# DCDC_LIN_CONN.net
KiCad netlist of a schematic drawn in Altium Designer
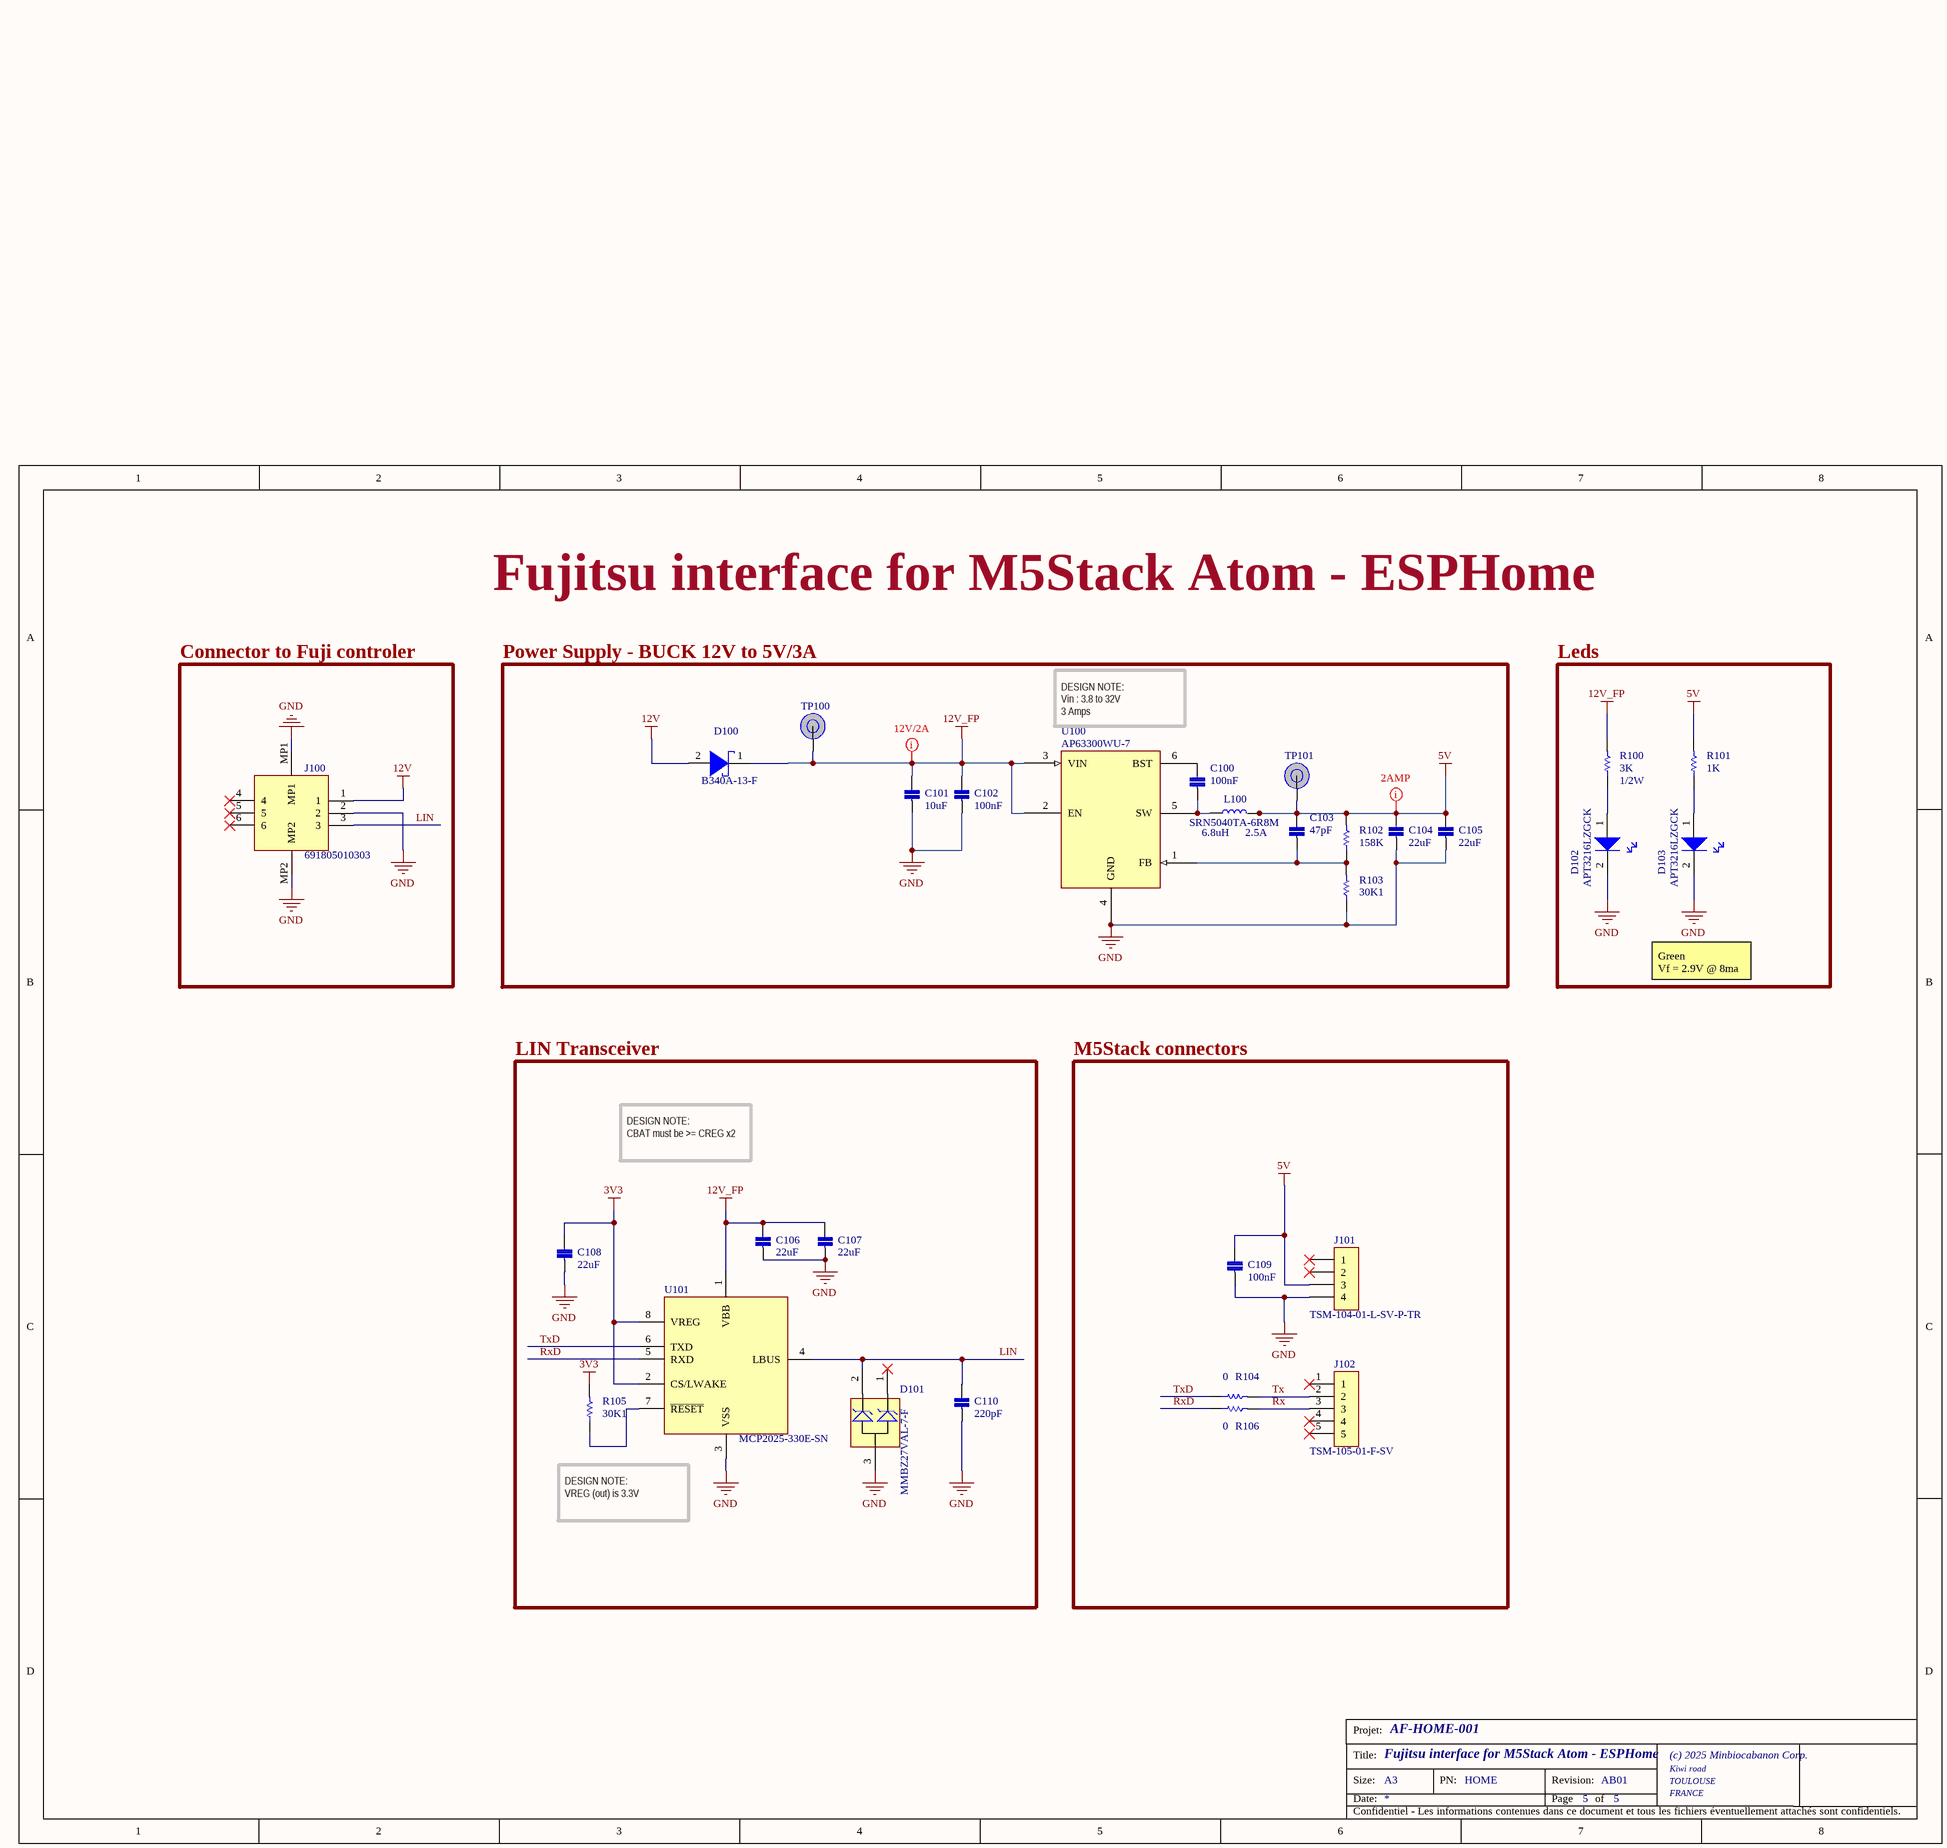
[diagram p0: DCDC_LIN_CONN.SchDoc]

(export (version "E")
  (design (tool "Eeschema 10.0.6"))
  (components
    (comp (ref "C100")
      (value "100nF")
      (footprint "0603_CAPA")
      (description "100nF_50V_0603_5%_X7R")
      (fields
        (field (name "MANUFACTURER PART NUMBER") "CAPA_CMS_100nF_50V_0603_5%_X7R")
        (field (name "TOLERANCE") "5%")
      )
      (libsource (lib "OILibrary") (part "CAPA_CMS-Generique"))
    )
    (comp (ref "C101")
      (value "10uF")
      (footprint "1206_CAPA")
      (description "10uF_50V_1206_10%_X7R")
      (fields
        (field (name "MANUFACTURER PART NUMBER") "CAPA_CMS_10uF_50V_1206_10%_X7R")
        (field (name "TOLERANCE") "10%")
      )
      (libsource (lib "OILibrary") (part "CAPA_CMS-Generique"))
    )
    (comp (ref "C102")
      (value "100nF")
      (footprint "0603_CAPA")
      (description "100nF_50V_0603_5%_X7R")
      (fields
        (field (name "MANUFACTURER PART NUMBER") "CAPA_CMS_100nF_50V_0603_5%_X7R")
        (field (name "TOLERANCE") "5%")
      )
      (libsource (lib "OILibrary") (part "CAPA_CMS-Generique"))
    )
    (comp (ref "C103")
      (value "47pF")
      (footprint "0603_CAPA")
      (description "47pF_50V_0603_5%_X7R")
      (fields
        (field (name "MANUFACTURER PART NUMBER") "CAPA_CMS_47pF_50V_0603_5%_X7R")
        (field (name "TOLERANCE") "5%")
      )
      (libsource (lib "OILibrary") (part "CAPA_CMS-Generique"))
    )
    (comp (ref "C104")
      (value "22uF")
      (footprint "0805_CAPA")
      (description "22uF_16V_0805_10%_X5R")
      (fields
        (field (name "MANUFACTURER PART NUMBER") "CAPA_CMS_22uF_16V_0805_10%_X5R")
        (field (name "TOLERANCE") "10%")
      )
      (libsource (lib "OILibrary") (part "CAPA_CMS-Generique"))
    )
    (comp (ref "C105")
      (value "22uF")
      (footprint "0805_CAPA")
      (description "22uF_16V_0805_10%_X5R")
      (fields
        (field (name "MANUFACTURER PART NUMBER") "CAPA_CMS_22uF_16V_0805_10%_X5R")
        (field (name "TOLERANCE") "10%")
      )
      (libsource (lib "OILibrary") (part "CAPA_CMS-Generique"))
    )
    (comp (ref "C106")
      (value "22uF")
      (footprint "0805_CAPA")
      (description "22uF_16V_0805_10%_X5R")
      (fields
        (field (name "MANUFACTURER PART NUMBER") "CAPA_CMS_22uF_16V_0805_10%_X5R")
        (field (name "TOLERANCE") "10%")
      )
      (libsource (lib "OILibrary") (part "CAPA_CMS-Generique"))
    )
    (comp (ref "C107")
      (value "22uF")
      (footprint "0805_CAPA")
      (description "22uF_16V_0805_10%_X5R")
      (fields
        (field (name "MANUFACTURER PART NUMBER") "CAPA_CMS_22uF_16V_0805_10%_X5R")
        (field (name "TOLERANCE") "10%")
      )
      (libsource (lib "OILibrary") (part "CAPA_CMS-Generique"))
    )
    (comp (ref "C108")
      (value "22uF")
      (footprint "0805_CAPA")
      (description "22uF_16V_0805_10%_X5R")
      (fields
        (field (name "MANUFACTURER PART NUMBER") "CAPA_CMS_22uF_16V_0805_10%_X5R")
        (field (name "TOLERANCE") "10%")
      )
      (libsource (lib "OILibrary") (part "CAPA_CMS-Generique"))
    )
    (comp (ref "C109")
      (value "100nF")
      (footprint "0603_CAPA")
      (description "100nF_50V_0603_5%_X7R")
      (fields
        (field (name "MANUFACTURER PART NUMBER") "CAPA_CMS_100nF_50V_0603_5%_X7R")
        (field (name "TOLERANCE") "5%")
      )
      (libsource (lib "OILibrary") (part "CAPA_CMS-Generique"))
    )
    (comp (ref "C110")
      (value "220pF")
      (footprint "0603_CAPA")
      (description "220pF_50V_0603_10%_X7R")
      (fields
        (field (name "MANUFACTURER PART NUMBER") "CAPA_CMS_220pF_50V_0603_10%_X7R")
        (field (name "TOLERANCE") "10%")
      )
      (libsource (lib "OILibrary") (part "CAPA_CMS-Generique"))
    )
    (comp (ref "D100")
      (value "B340A-13-F")
      (footprint "DIODE_B340A-13-F")
      (description "Diodes et redresseurs Schottky 40V 3A")
      (fields (field (name "MANUFACTURER") "Diodes"))
      (libsource (lib "OILibrary") (part "DIODE_SCHOTTKY_CMS-Generique"))
    )
    (comp (ref "D101")
      (value "MMBZ27VAL-7-F")
      (footprint "ESD_MMBZ27VAL-7-F")
      (description "Suppresseurs ESD / diodes TVS 27V 225mW")
      (libsource (lib "OILibrary") (part "ESD_MMBZ27VAL-7-F"))
    )
    (comp (ref "D102")
      (value "APT3216LZGCK")
      (footprint "LED_APT3216LZGCK")
      (description "LED CMS Green 3.2x1.6mm")
      (fields (field (name "MANUFACTURER") "Kingbright"))
      (libsource (lib "OILibrary") (part "LED_CMS-Generique"))
    )
    (comp (ref "D103")
      (value "APT3216LZGCK")
      (footprint "LED_APT3216LZGCK")
      (description "LED CMS Green 3.2x1.6mm")
      (fields (field (name "MANUFACTURER") "Kingbright"))
      (libsource (lib "OILibrary") (part "LED_CMS-Generique"))
    )
    (comp (ref "J100")
      (value "691805010303")
      (footprint "691805010303")
      (description "WR-TBL Series 8050 - 3 pins 2.50 mm Screwless SMT")
      (fields (field (name "MANUFACTURER") "Wurth Elektronik"))
      (libsource (lib "OILibrary") (part "691805010303"))
    )
    (comp (ref "J101")
      (value "TSM-104-01-L-SV-P-TR")
      (footprint "TSM-104-01-L-SV-P-TR")
      (description "Header male SMD 1x4")
      (fields (field (name "MANUFACTURER") "Samtec"))
      (libsource (lib "OILibrary") (part "TSM-104-01-L-SV-P-TR"))
    )
    (comp (ref "J102")
      (value "TSM-105-01-F-SV")
      (footprint "TSM-105-01-F-SV")
      (description "Header male SMD 1x5")
      (fields (field (name "MANUFACTURER") "SAMTEC"))
      (libsource (lib "OILibrary") (part "TSM-105-01-F-SV"))
    )
    (comp (ref "L100")
      (value "SRN5040TA-6R8M")
      (footprint "INDUCTOR_652-SRN5040TA-100M")
      (description "Inductance fixes 6.8uH 2.5A")
      (fields
        (field (name "MANUFACTURER") "Bourns")
        (field (name "INDUCTANCE") "6.8uH")
        (field (name "CURRENT RATING") "2.5A")
      )
      (libsource (lib "OILibrary") (part "INDUCTOR_CMS-Generique"))
    )
    (comp (ref "R100")
      (value "3K")
      (footprint "0805_RES")
      (description "3K_1/8W_0805_1%")
      (fields
        (field (name "MANUFACTURER PART NUMBER") "RES_CMS_3K_1/8W_0805_1%")
        (field (name "TOLERANCE") "1%")
      )
      (libsource (lib "OILibrary") (part "RES_CMS-Generique"))
    )
    (comp (ref "R101")
      (value "1K")
      (footprint "0603_RES")
      (description "1K_1/10W_0603_1%")
      (fields
        (field (name "MANUFACTURER PART NUMBER") "RES_CMS_1K_1/10W_0603_1%")
        (field (name "TOLERANCE") "1%")
      )
      (libsource (lib "OILibrary") (part "RES_CMS-Generique"))
    )
    (comp (ref "R102")
      (value "158K")
      (footprint "0603_RES")
      (description "158K_1/16W_0603_1%")
      (fields
        (field (name "MANUFACTURER PART NUMBER") "RES_CMS_158K_1/16W_0603_1%")
        (field (name "TOLERANCE") "1%")
      )
      (libsource (lib "OILibrary") (part "RES_CMS-Generique"))
    )
    (comp (ref "R103")
      (value "30K1")
      (footprint "0603_RES")
      (description "30K1_1/10W_0603_1%")
      (fields
        (field (name "MANUFACTURER PART NUMBER") "RES_CMS_30K1_1/10W_0603_1%")
        (field (name "TOLERANCE") "1%")
      )
      (libsource (lib "OILibrary") (part "RES_CMS-Generique"))
    )
    (comp (ref "R104")
      (value "0")
      (footprint "0603_RES")
      (description "0_1/10W_0603_1%")
      (fields
        (field (name "MANUFACTURER PART NUMBER") "RES_CMS_0_1/10W_0603_1%")
        (field (name "TOLERANCE") "1%")
      )
      (libsource (lib "OILibrary") (part "RES_CMS-Generique"))
    )
    (comp (ref "R105")
      (value "30K1")
      (footprint "0603_RES")
      (description "30K1_1/10W_0603_1%")
      (fields
        (field (name "MANUFACTURER PART NUMBER") "RES_CMS_30K1_1/10W_0603_1%")
        (field (name "TOLERANCE") "1%")
      )
      (libsource (lib "OILibrary") (part "RES_CMS-Generique"))
    )
    (comp (ref "R106")
      (value "0")
      (footprint "0603_RES")
      (description "0_1/10W_0603_1%")
      (fields
        (field (name "MANUFACTURER PART NUMBER") "RES_CMS_0_1/10W_0603_1%")
        (field (name "TOLERANCE") "1%")
      )
      (libsource (lib "OILibrary") (part "RES_CMS-Generique"))
    )
    (comp (ref "TP100")
      (value "5V_BUCK")
      (footprint "PTEST")
      (description "Test point")
      (fields (field (name "MANUFACTURER") "OPENINDUS") (field (name "MANUFACTURER PART NUMBER") "PTEST"))
      (libsource (lib "OILibrary") (part "PTEST"))
    )
    (comp (ref "TP101")
      (value "5V_BUCK")
      (footprint "PTEST")
      (description "Test point")
      (fields (field (name "MANUFACTURER") "OPENINDUS") (field (name "MANUFACTURER PART NUMBER") "PTEST"))
      (libsource (lib "OILibrary") (part "PTEST"))
    )
    (comp (ref "U100")
      (value "AP63300WU-7")
      (footprint "POWER_BUCK_AP63300WU-7")
      (description "Régulateurs de tension de commutation DCDC Conv HV Buck TSOT26 T&R 3K")
      (fields (field (name "MANUFACTURER") "Diodes Incorporated"))
      (libsource (lib "OILibrary") (part "POWER_BUCK_AP63300WU-7"))
    )
    (comp (ref "U101")
      (value "MCP2025-330E-SN")
      (footprint "MCP2025-330E-SN")
      (description "LIN Transceiver with Voltage Regulator SOIC 3.3V")
      (fields
        (field (name "MANUFACTURER PART NUMBER") "MCP2025-330E/SN")
        (field (name "MANUFACTURER") "Microchip")
      )
      (libsource (lib "OILibrary") (part "MCP2025-330E-SN"))
    )
  )
  (nets
    (net (code "1") (name "/LIN") (class "Default")
      (node (ref "C110") (pin "1") (pinfunction "1_1") (pintype "passive"))
      (node (ref "D101") (pin "2") (pinfunction "2_2") (pintype "passive"))
      (node (ref "J100") (pin "3") (pinfunction "3_3") (pintype "passive"))
      (node (ref "U101") (pin "4") (pinfunction "LBUS_4") (pintype "passive"))
    )
    (net (code "2") (name "/Rx") (class "Default")
      (node (ref "J102") (pin "3") (pinfunction "3_3") (pintype "passive"))
      (node (ref "R106") (pin "2") (pinfunction "2_2") (pintype "passive"))
    )
    (net (code "3") (name "/RxD") (class "Default")
      (node (ref "R106") (pin "1") (pinfunction "1_1") (pintype "passive"))
      (node (ref "U101") (pin "5") (pinfunction "RXD_5") (pintype "passive"))
    )
    (net (code "4") (name "/Tx") (class "Default")
      (node (ref "J102") (pin "2") (pinfunction "2_2") (pintype "passive"))
      (node (ref "R104") (pin "2") (pinfunction "2_2") (pintype "passive"))
    )
    (net (code "5") (name "/TxD") (class "Default")
      (node (ref "R104") (pin "1") (pinfunction "1_1") (pintype "passive"))
      (node (ref "U101") (pin "6") (pinfunction "TXD_6") (pintype "passive"))
    )
    (net (code "6") (name "3V3") (class "Default")
      (node (ref "C108") (pin "1") (pinfunction "1_1") (pintype "passive"))
      (node (ref "R105") (pin "2") (pinfunction "2_2") (pintype "passive"))
      (node (ref "U101") (pin "2") (pinfunction "CS/LWAKE_2") (pintype "passive"))
      (node (ref "U101") (pin "8") (pinfunction "VREG_8") (pintype "passive"))
    )
    (net (code "7") (name "5V") (class "Default")
      (node (ref "C103") (pin "1") (pinfunction "1_1") (pintype "passive"))
      (node (ref "C104") (pin "1") (pinfunction "1_1") (pintype "passive"))
      (node (ref "C105") (pin "1") (pinfunction "1_1") (pintype "passive"))
      (node (ref "C109") (pin "1") (pinfunction "1_1") (pintype "passive"))
      (node (ref "J101") (pin "3") (pinfunction "3_3") (pintype "passive"))
      (node (ref "L100") (pin "2") (pinfunction "2_2") (pintype "passive"))
      (node (ref "R101") (pin "2") (pinfunction "2_2") (pintype "passive"))
      (node (ref "R102") (pin "2") (pinfunction "2_2") (pintype "passive"))
      (node (ref "TP101") (pin "1") (pinfunction "1_1") (pintype "passive"))
    )
    (net (code "8") (name "12V") (class "Default")
      (node (ref "D100") (pin "2") (pinfunction "A_2") (pintype "passive"))
      (node (ref "J100") (pin "1") (pinfunction "1_1") (pintype "passive"))
    )
    (net (code "9") (name "12V_FP") (class "Default")
      (node (ref "C101") (pin "1") (pinfunction "1_1") (pintype "passive"))
      (node (ref "C102") (pin "1") (pinfunction "1_1") (pintype "passive"))
      (node (ref "C106") (pin "1") (pinfunction "1_1") (pintype "passive"))
      (node (ref "C107") (pin "1") (pinfunction "1_1") (pintype "passive"))
      (node (ref "D100") (pin "1") (pinfunction "K_1") (pintype "passive"))
      (node (ref "R100") (pin "2") (pinfunction "2_2") (pintype "passive"))
      (node (ref "TP100") (pin "1") (pinfunction "1_1") (pintype "passive"))
      (node (ref "U100") (pin "2") (pinfunction "EN_2") (pintype "passive"))
      (node (ref "U100") (pin "3") (pinfunction "VIN_3") (pintype "input"))
      (node (ref "U101") (pin "1") (pinfunction "VBB_1") (pintype "passive"))
    )
    (net (code "10") (name "GND") (class "Default")
      (node (ref "C101") (pin "2") (pinfunction "2_2") (pintype "passive"))
      (node (ref "C102") (pin "2") (pinfunction "2_2") (pintype "passive"))
      (node (ref "C104") (pin "2") (pinfunction "2_2") (pintype "passive"))
      (node (ref "C105") (pin "2") (pinfunction "2_2") (pintype "passive"))
      (node (ref "C106") (pin "2") (pinfunction "2_2") (pintype "passive"))
      (node (ref "C107") (pin "2") (pinfunction "2_2") (pintype "passive"))
      (node (ref "C108") (pin "2") (pinfunction "2_2") (pintype "passive"))
      (node (ref "C109") (pin "2") (pinfunction "2_2") (pintype "passive"))
      (node (ref "C110") (pin "2") (pinfunction "2_2") (pintype "passive"))
      (node (ref "D101") (pin "3") (pinfunction "3_3") (pintype "passive"))
      (node (ref "D102") (pin "2") (pinfunction "2_2") (pintype "passive"))
      (node (ref "D103") (pin "2") (pinfunction "2_2") (pintype "passive"))
      (node (ref "J100") (pin "2") (pinfunction "2_2") (pintype "passive"))
      (node (ref "J100") (pin "MP1") (pinfunction "MP1_MP1") (pintype "passive"))
      (node (ref "J100") (pin "MP2") (pinfunction "MP2_MP2") (pintype "passive"))
      (node (ref "J101") (pin "4") (pinfunction "4_4") (pintype "passive"))
      (node (ref "R103") (pin "1") (pinfunction "1_1") (pintype "passive"))
      (node (ref "U100") (pin "4") (pinfunction "GND_4") (pintype "passive"))
      (node (ref "U101") (pin "3") (pinfunction "VSS_3") (pintype "passive"))
    )
    (net (code "11") (name "Net-(D102-Pad1)") (class "Default")
      (node (ref "D102") (pin "1") (pinfunction "1_1") (pintype "passive"))
      (node (ref "R100") (pin "1") (pinfunction "1_1") (pintype "passive"))
    )
    (net (code "12") (name "Net-(D103-Pad1)") (class "Default")
      (node (ref "D103") (pin "1") (pinfunction "1_1") (pintype "passive"))
      (node (ref "R101") (pin "1") (pinfunction "1_1") (pintype "passive"))
    )
    (net (code "13") (name "Net-(U100-BST)") (class "Default")
      (node (ref "C100") (pin "1") (pinfunction "1_1") (pintype "passive"))
      (node (ref "U100") (pin "6") (pinfunction "BST_6") (pintype "passive"))
    )
    (net (code "14") (name "Net-(U100-FB)") (class "Default")
      (node (ref "C103") (pin "2") (pinfunction "2_2") (pintype "passive"))
      (node (ref "R102") (pin "1") (pinfunction "1_1") (pintype "passive"))
      (node (ref "R103") (pin "2") (pinfunction "2_2") (pintype "passive"))
      (node (ref "U100") (pin "1") (pinfunction "FB_1") (pintype "input"))
    )
    (net (code "15") (name "Net-(U100-SW)") (class "Default")
      (node (ref "C100") (pin "2") (pinfunction "2_2") (pintype "passive"))
      (node (ref "L100") (pin "1") (pinfunction "1_1") (pintype "passive"))
      (node (ref "U100") (pin "5") (pinfunction "SW_5") (pintype "passive"))
    )
    (net (code "16") (name "Net-(U101-~{RESET})") (class "Default")
      (node (ref "R105") (pin "1") (pinfunction "1_1") (pintype "passive"))
      (node (ref "U101") (pin "7") (pinfunction "~{RESET}_7") (pintype "passive"))
    )
    (net (code "17") (name "unconnected-(D101-Pad1)") (class "Default")
      (node (ref "D101") (pin "1") (pinfunction "1_1") (pintype "passive+no_connect"))
    )
    (net (code "18") (name "unconnected-(J100-Pad4)") (class "Default")
      (node (ref "J100") (pin "4") (pinfunction "4_4") (pintype "passive+no_connect"))
    )
    (net (code "19") (name "unconnected-(J100-Pad5)") (class "Default")
      (node (ref "J100") (pin "5") (pinfunction "5_5") (pintype "passive+no_connect"))
    )
    (net (code "20") (name "unconnected-(J100-Pad6)") (class "Default")
      (node (ref "J100") (pin "6") (pinfunction "6_6") (pintype "passive+no_connect"))
    )
    (net (code "21") (name "unconnected-(J101-Pad1)") (class "Default")
      (node (ref "J101") (pin "1") (pinfunction "1_1") (pintype "passive+no_connect"))
    )
    (net (code "22") (name "unconnected-(J101-Pad2)") (class "Default")
      (node (ref "J101") (pin "2") (pinfunction "2_2") (pintype "passive+no_connect"))
    )
    (net (code "23") (name "unconnected-(J102-Pad1)") (class "Default")
      (node (ref "J102") (pin "1") (pinfunction "1_1") (pintype "passive+no_connect"))
    )
    (net (code "24") (name "unconnected-(J102-Pad4)") (class "Default")
      (node (ref "J102") (pin "4") (pinfunction "4_4") (pintype "passive+no_connect"))
    )
    (net (code "25") (name "unconnected-(J102-Pad5)") (class "Default")
      (node (ref "J102") (pin "5") (pinfunction "5_5") (pintype "passive+no_connect"))
    )
  )
)
